# Yaesu_to_CIV.net
KiCad netlist of a schematic drawn in EAGLE
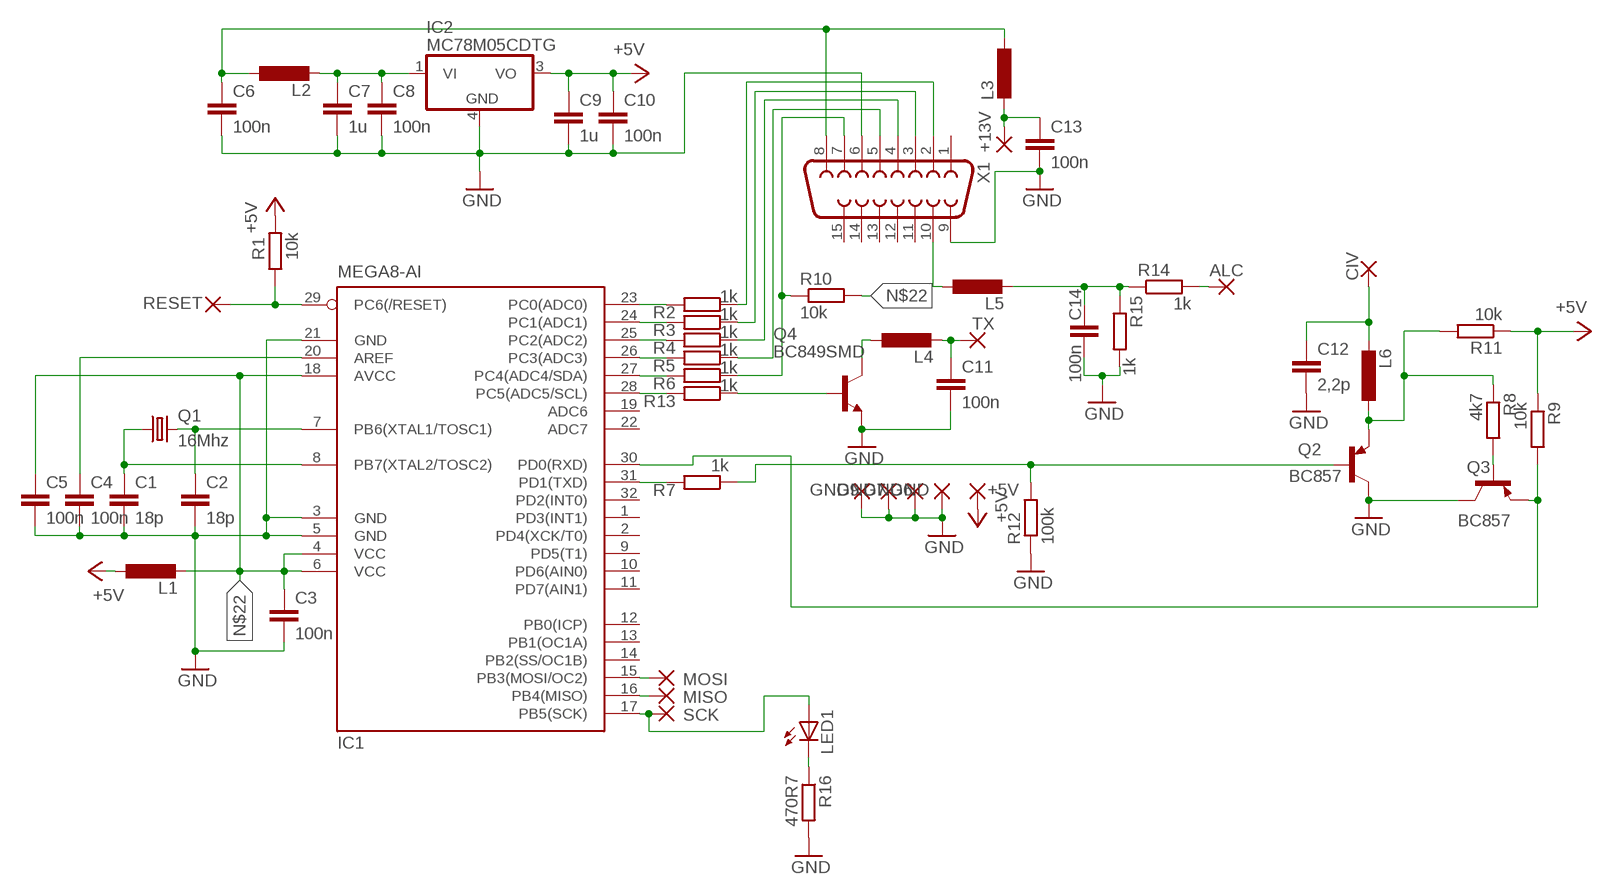
[diagram p0: schematic, sheet 1]

(export (version "E")
  (design (tool "Eeschema 10.0.6"))
  (components
    (comp (ref "+5V")
      (value "SMD2")
      (footprint "eagle-import:SMD1,27-2,54")
      (libsource (lib "eagle-import") (part "SMD2"))
    )
    (comp (ref "+13V")
      (value "SMD2")
      (footprint "eagle-import:SMD1,27-2,54")
      (libsource (lib "eagle-import") (part "SMD2"))
    )
    (comp (ref "ALC")
      (value "SMD2")
      (footprint "eagle-import:SMD1,27-2,54")
      (libsource (lib "eagle-import") (part "SMD2"))
    )
    (comp (ref "C1")
      (value "18p")
      (footprint "eagle-import:C0603K")
      (libsource (lib "eagle-import") (part "C-EUC0603K"))
    )
    (comp (ref "C2")
      (value "18p")
      (footprint "eagle-import:C0603K")
      (libsource (lib "eagle-import") (part "C-EUC0603K"))
    )
    (comp (ref "C3")
      (value "100n")
      (footprint "eagle-import:C0603K")
      (libsource (lib "eagle-import") (part "C-EUC0603K"))
    )
    (comp (ref "C4")
      (value "100n")
      (footprint "eagle-import:C0603K")
      (libsource (lib "eagle-import") (part "C-EUC0603K"))
    )
    (comp (ref "C5")
      (value "100n")
      (footprint "eagle-import:C0603K")
      (libsource (lib "eagle-import") (part "C-EUC0603K"))
    )
    (comp (ref "C6")
      (value "100n")
      (footprint "eagle-import:C0603K")
      (libsource (lib "eagle-import") (part "C-EUC0603K"))
    )
    (comp (ref "C7")
      (value "1u")
      (footprint "eagle-import:C0805K")
      (libsource (lib "eagle-import") (part "C-EUC0805K"))
    )
    (comp (ref "C8")
      (value "100n")
      (footprint "eagle-import:C0603K")
      (libsource (lib "eagle-import") (part "C-EUC0603K"))
    )
    (comp (ref "C9")
      (value "1u")
      (footprint "eagle-import:C0805K")
      (libsource (lib "eagle-import") (part "C-EUC0805K"))
    )
    (comp (ref "C10")
      (value "100n")
      (footprint "eagle-import:C0603K")
      (libsource (lib "eagle-import") (part "C-EUC0603K"))
    )
    (comp (ref "C11")
      (value "100n")
      (footprint "eagle-import:C0603K")
      (libsource (lib "eagle-import") (part "C-EUC0603K"))
    )
    (comp (ref "C12")
      (value "2,2p")
      (footprint "eagle-import:C0603K")
      (libsource (lib "eagle-import") (part "C-EUC0603K"))
    )
    (comp (ref "C13")
      (value "100n")
      (footprint "eagle-import:C0603K")
      (libsource (lib "eagle-import") (part "C-EUC0603K"))
    )
    (comp (ref "C14")
      (value "100n")
      (footprint "eagle-import:C0603K")
      (libsource (lib "eagle-import") (part "C-EUC0603K"))
    )
    (comp (ref "CIV")
      (value "SMD2")
      (footprint "eagle-import:SMD1,27-2,54")
      (libsource (lib "eagle-import") (part "SMD2"))
    )
    (comp (ref "GND")
      (value "SMD2")
      (footprint "eagle-import:SMD1,27-2,54")
      (libsource (lib "eagle-import") (part "SMD2"))
    )
    (comp (ref "GND6")
      (value "SMD2")
      (footprint "eagle-import:SMD1,27-2,54")
      (libsource (lib "eagle-import") (part "SMD2"))
    )
    (comp (ref "GND7")
      (value "SMD2")
      (footprint "eagle-import:SMD1,27-2,54")
      (libsource (lib "eagle-import") (part "SMD2"))
    )
    (comp (ref "GND9")
      (value "SMD2")
      (footprint "eagle-import:SMD1,27-2,54")
      (libsource (lib "eagle-import") (part "SMD2"))
    )
    (comp (ref "IC1")
      (value "MEGA8-AI")
      (footprint "eagle-import:TQFP32-08")
      (fields (field (name "MPN") "ATMEGA8-16AU"))
      (libsource (lib "eagle-import") (part "MEGA8-AI"))
    )
    (comp (ref "IC2")
      (value "MC78M05CDTG")
      (footprint "eagle-import:DPACK_3")
      (libsource (lib "eagle-import") (part "MC78M05CDTG"))
    )
    (comp (ref "L1")
      (value "L-EUL2012C")
      (footprint "eagle-import:L2012C")
      (libsource (lib "eagle-import") (part "L-EUL2012C"))
    )
    (comp (ref "L2")
      (value "L-EUL1812")
      (footprint "eagle-import:L1812")
      (libsource (lib "eagle-import") (part "L-EUL1812"))
    )
    (comp (ref "L3")
      (value "L-EUL1812")
      (footprint "eagle-import:L1812")
      (libsource (lib "eagle-import") (part "L-EUL1812"))
    )
    (comp (ref "L4")
      (value "L-EUL2012C")
      (footprint "eagle-import:L2012C")
      (libsource (lib "eagle-import") (part "L-EUL2012C"))
    )
    (comp (ref "L5")
      (value "L-EUL2012C")
      (footprint "eagle-import:L2012C")
      (libsource (lib "eagle-import") (part "L-EUL2012C"))
    )
    (comp (ref "L6")
      (value "L-EUL2012C")
      (footprint "eagle-import:L2012C")
      (libsource (lib "eagle-import") (part "L-EUL2012C"))
    )
    (comp (ref "LED1")
      (value "LEDCHIP-LED0603")
      (footprint "eagle-import:CHIP-LED0603")
      (libsource (lib "eagle-import") (part "LEDCHIP-LED0603"))
    )
    (comp (ref "MISO")
      (value "SMD2")
      (footprint "eagle-import:SMD1,27-2,54")
      (libsource (lib "eagle-import") (part "SMD2"))
    )
    (comp (ref "MOSI")
      (value "SMD2")
      (footprint "eagle-import:SMD1,27-2,54")
      (libsource (lib "eagle-import") (part "SMD2"))
    )
    (comp (ref "Q1")
      (value "16Mhz")
      (footprint "eagle-import:CTS406")
      (libsource (lib "eagle-import") (part "CRYSTALCTS406"))
    )
    (comp (ref "Q2")
      (value "BC857")
      (footprint "eagle-import:SOT23-BEC")
      (libsource (lib "eagle-import") (part "BC857SMDA"))
    )
    (comp (ref "Q3")
      (value "BC857")
      (footprint "eagle-import:SOT23-BEC")
      (libsource (lib "eagle-import") (part "BC857SMDA"))
    )
    (comp (ref "Q4")
      (value "BC849SMD")
      (footprint "eagle-import:SOT23-BEC")
      (libsource (lib "eagle-import") (part "BC849SMD"))
    )
    (comp (ref "R1")
      (value "10k")
      (footprint "eagle-import:R0603")
      (libsource (lib "eagle-import") (part "R-EU_R0603"))
    )
    (comp (ref "R2")
      (value "1k")
      (footprint "eagle-import:R0603")
      (libsource (lib "eagle-import") (part "R-EU_R0603"))
    )
    (comp (ref "R3")
      (value "1k")
      (footprint "eagle-import:R0603")
      (libsource (lib "eagle-import") (part "R-EU_R0603"))
    )
    (comp (ref "R4")
      (value "1k")
      (footprint "eagle-import:R0603")
      (libsource (lib "eagle-import") (part "R-EU_R0603"))
    )
    (comp (ref "R5")
      (value "1k")
      (footprint "eagle-import:R0603")
      (libsource (lib "eagle-import") (part "R-EU_R0603"))
    )
    (comp (ref "R6")
      (value "1k")
      (footprint "eagle-import:R0603")
      (libsource (lib "eagle-import") (part "R-EU_R0603"))
    )
    (comp (ref "R7")
      (value "1k")
      (footprint "eagle-import:R0603")
      (libsource (lib "eagle-import") (part "R-EU_R0603"))
    )
    (comp (ref "R8")
      (value "4k7")
      (footprint "eagle-import:R0603")
      (libsource (lib "eagle-import") (part "R-EU_R0603"))
    )
    (comp (ref "R9")
      (value "10k")
      (footprint "eagle-import:R0603")
      (libsource (lib "eagle-import") (part "R-EU_R0603"))
    )
    (comp (ref "R10")
      (value "10k")
      (footprint "eagle-import:R0603")
      (libsource (lib "eagle-import") (part "R-EU_R0603"))
    )
    (comp (ref "R11")
      (value "10k")
      (footprint "eagle-import:R0603")
      (libsource (lib "eagle-import") (part "R-EU_R0603"))
    )
    (comp (ref "R12")
      (value "100k")
      (footprint "eagle-import:R0603")
      (libsource (lib "eagle-import") (part "R-EU_R0603"))
    )
    (comp (ref "R13")
      (value "1k")
      (footprint "eagle-import:R0603")
      (libsource (lib "eagle-import") (part "R-EU_R0603"))
    )
    (comp (ref "R14")
      (value "1k")
      (footprint "eagle-import:R0603")
      (libsource (lib "eagle-import") (part "R-EU_R0603"))
    )
    (comp (ref "R15")
      (value "1k")
      (footprint "eagle-import:R0603")
      (libsource (lib "eagle-import") (part "R-EU_R0603"))
    )
    (comp (ref "R16")
      (value "470R7")
      (footprint "eagle-import:R0603")
      (libsource (lib "eagle-import") (part "R-EU_R0603"))
    )
    (comp (ref "RESET")
      (value "SMD2")
      (footprint "eagle-import:SMD1,27-2,54")
      (libsource (lib "eagle-import") (part "SMD2"))
    )
    (comp (ref "SCK")
      (value "SMD2")
      (footprint "eagle-import:SMD1,27-2,54")
      (libsource (lib "eagle-import") (part "SMD2"))
    )
    (comp (ref "TX")
      (value "SMD2")
      (footprint "eagle-import:SMD1,27-2,54")
      (libsource (lib "eagle-import") (part "SMD2"))
    )
    (comp (ref "X1")
      (value "F15D")
      (footprint "eagle-import:F15D")
      (libsource (lib "eagle-import") (part "F15D"))
    )
  )
  (nets
    (net (code "1") (name "+5V") (class "Default")
      (node (ref "+5V") (pin "1") (pinfunction "P_1") (pintype "passive"))
      (node (ref "C10") (pin "1") (pinfunction "1_1") (pintype "passive"))
      (node (ref "C9") (pin "1") (pinfunction "1_1") (pintype "passive"))
      (node (ref "IC2") (pin "3") (pinfunction "VO_3") (pintype "passive"))
      (node (ref "L1") (pin "1") (pinfunction "1_1") (pintype "passive"))
      (node (ref "R1") (pin "2") (pinfunction "2_2") (pintype "passive"))
      (node (ref "R11") (pin "1") (pinfunction "1_1") (pintype "passive"))
      (node (ref "R9") (pin "1") (pinfunction "1_1") (pintype "passive"))
    )
    (net (code "2") (name "GND") (class "Default")
      (node (ref "C1") (pin "2") (pinfunction "2_2") (pintype "passive"))
      (node (ref "C10") (pin "2") (pinfunction "2_2") (pintype "passive"))
      (node (ref "C11") (pin "2") (pinfunction "2_2") (pintype "passive"))
      (node (ref "C12") (pin "2") (pinfunction "2_2") (pintype "passive"))
      (node (ref "C13") (pin "2") (pinfunction "2_2") (pintype "passive"))
      (node (ref "C14") (pin "2") (pinfunction "2_2") (pintype "passive"))
      (node (ref "C2") (pin "2") (pinfunction "2_2") (pintype "passive"))
      (node (ref "C3") (pin "2") (pinfunction "2_2") (pintype "passive"))
      (node (ref "C4") (pin "2") (pinfunction "2_2") (pintype "passive"))
      (node (ref "C5") (pin "2") (pinfunction "2_2") (pintype "passive"))
      (node (ref "C6") (pin "2") (pinfunction "2_2") (pintype "passive"))
      (node (ref "C7") (pin "2") (pinfunction "2_2") (pintype "passive"))
      (node (ref "C8") (pin "2") (pinfunction "2_2") (pintype "passive"))
      (node (ref "C9") (pin "2") (pinfunction "2_2") (pintype "passive"))
      (node (ref "GND") (pin "1") (pinfunction "P_1") (pintype "passive"))
      (node (ref "GND6") (pin "1") (pinfunction "P_1") (pintype "passive"))
      (node (ref "GND7") (pin "1") (pinfunction "P_1") (pintype "passive"))
      (node (ref "GND9") (pin "1") (pinfunction "P_1") (pintype "passive"))
      (node (ref "IC1") (pin "21") (pinfunction "GND_21") (pintype "power_in"))
      (node (ref "IC1") (pin "3") (pinfunction "GND_3") (pintype "power_in"))
      (node (ref "IC1") (pin "5") (pinfunction "GND_5") (pintype "power_in"))
      (node (ref "IC2") (pin "4") (pinfunction "GND_4") (pintype "passive"))
      (node (ref "Q2") (pin "C") (pinfunction "C_C") (pintype "passive"))
      (node (ref "Q3") (pin "C") (pinfunction "C_C") (pintype "passive"))
      (node (ref "Q4") (pin "E") (pinfunction "E_E") (pintype "passive"))
      (node (ref "R12") (pin "1") (pinfunction "1_1") (pintype "passive"))
      (node (ref "R15") (pin "2") (pinfunction "2_2") (pintype "passive"))
      (node (ref "R16") (pin "2") (pinfunction "2_2") (pintype "passive"))
      (node (ref "X1") (pin "6") (pinfunction "6_6") (pintype "passive"))
      (node (ref "X1") (pin "9") (pinfunction "9_9") (pintype "passive"))
    )
    (net (code "3") (name "N$22") (class "Default")
      (node (ref "C3") (pin "1") (pinfunction "1_1") (pintype "passive"))
      (node (ref "C5") (pin "1") (pinfunction "1_1") (pintype "passive"))
      (node (ref "IC1") (pin "18") (pinfunction "AVCC_18") (pintype "power_in"))
      (node (ref "IC1") (pin "4") (pinfunction "VCC_4") (pintype "power_in"))
      (node (ref "IC1") (pin "6") (pinfunction "VCC_6") (pintype "power_in"))
      (node (ref "L1") (pin "2") (pinfunction "2_2") (pintype "passive"))
      (node (ref "R10") (pin "2") (pinfunction "2_2") (pintype "passive"))
    )
    (net (code "4") (name "Net-(+13V-P)") (class "Default")
      (node (ref "+13V") (pin "1") (pinfunction "P_1") (pintype "passive"))
      (node (ref "C13") (pin "1") (pinfunction "1_1") (pintype "passive"))
      (node (ref "L3") (pin "2") (pinfunction "2_2") (pintype "passive"))
    )
    (net (code "5") (name "Net-(ALC-P)") (class "Default")
      (node (ref "ALC") (pin "1") (pinfunction "P_1") (pintype "passive"))
      (node (ref "R14") (pin "2") (pinfunction "2_2") (pintype "passive"))
    )
    (net (code "6") (name "Net-(C6-Pad1)") (class "Default")
      (node (ref "C6") (pin "1") (pinfunction "1_1") (pintype "passive"))
      (node (ref "L2") (pin "1") (pinfunction "1_1") (pintype "passive"))
      (node (ref "L3") (pin "1") (pinfunction "1_1") (pintype "passive"))
      (node (ref "X1") (pin "8") (pinfunction "8_8") (pintype "passive"))
    )
    (net (code "7") (name "Net-(C14-Pad1)") (class "Default")
      (node (ref "C14") (pin "1") (pinfunction "1_1") (pintype "passive"))
      (node (ref "L5") (pin "2") (pinfunction "2_2") (pintype "passive"))
      (node (ref "R14") (pin "1") (pinfunction "1_1") (pintype "passive"))
      (node (ref "R15") (pin "1") (pinfunction "1_1") (pintype "passive"))
    )
    (net (code "8") (name "Net-(CIV-P)") (class "Default")
      (node (ref "C12") (pin "1") (pinfunction "1_1") (pintype "passive"))
      (node (ref "CIV") (pin "1") (pinfunction "P_1") (pintype "passive"))
      (node (ref "L6") (pin "2") (pinfunction "2_2") (pintype "passive"))
    )
    (net (code "9") (name "Net-(IC1-AREF)") (class "Default")
      (node (ref "C4") (pin "1") (pinfunction "1_1") (pintype "passive"))
      (node (ref "IC1") (pin "20") (pinfunction "AREF_20") (pintype "passive"))
    )
    (net (code "10") (name "Net-(IC1-PB3(MOSI{slash}OC2))") (class "Default")
      (node (ref "IC1") (pin "15") (pinfunction "PB3(MOSI/OC2)_15") (pintype "bidirectional"))
      (node (ref "MOSI") (pin "1") (pinfunction "P_1") (pintype "passive"))
    )
    (net (code "11") (name "Net-(IC1-PB4(MISO))") (class "Default")
      (node (ref "IC1") (pin "16") (pinfunction "PB4(MISO)_16") (pintype "bidirectional"))
      (node (ref "MISO") (pin "1") (pinfunction "P_1") (pintype "passive"))
    )
    (net (code "12") (name "Net-(IC1-PB5(SCK))") (class "Default")
      (node (ref "IC1") (pin "17") (pinfunction "PB5(SCK)_17") (pintype "bidirectional"))
      (node (ref "LED1") (pin "A") (pinfunction "A_A") (pintype "passive"))
      (node (ref "SCK") (pin "1") (pinfunction "P_1") (pintype "passive"))
    )
    (net (code "13") (name "Net-(IC1-PB6(XTAL1{slash}TOSC1))") (class "Default")
      (node (ref "C2") (pin "1") (pinfunction "1_1") (pintype "passive"))
      (node (ref "IC1") (pin "7") (pinfunction "PB6(XTAL1/TOSC1)_7") (pintype "bidirectional"))
      (node (ref "Q1") (pin "3") (pinfunction "2_3") (pintype "passive"))
    )
    (net (code "14") (name "Net-(IC1-PB7(XTAL2{slash}TOSC2))") (class "Default")
      (node (ref "C1") (pin "1") (pinfunction "1_1") (pintype "passive"))
      (node (ref "IC1") (pin "8") (pinfunction "PB7(XTAL2/TOSC2)_8") (pintype "bidirectional"))
      (node (ref "Q1") (pin "1") (pinfunction "1_1") (pintype "passive"))
    )
    (net (code "15") (name "Net-(IC1-PC0(ADC0))") (class "Default")
      (node (ref "IC1") (pin "23") (pinfunction "PC0(ADC0)_23") (pintype "bidirectional"))
      (node (ref "R2") (pin "2") (pinfunction "2_2") (pintype "passive"))
    )
    (net (code "16") (name "Net-(IC1-PC1(ADC1))") (class "Default")
      (node (ref "IC1") (pin "24") (pinfunction "PC1(ADC1)_24") (pintype "bidirectional"))
      (node (ref "R3") (pin "2") (pinfunction "2_2") (pintype "passive"))
    )
    (net (code "17") (name "Net-(IC1-PC2(ADC2))") (class "Default")
      (node (ref "IC1") (pin "25") (pinfunction "PC2(ADC2)_25") (pintype "bidirectional"))
      (node (ref "R4") (pin "2") (pinfunction "2_2") (pintype "passive"))
    )
    (net (code "18") (name "Net-(IC1-PC3(ADC3))") (class "Default")
      (node (ref "IC1") (pin "26") (pinfunction "PC3(ADC3)_26") (pintype "bidirectional"))
      (node (ref "R5") (pin "2") (pinfunction "2_2") (pintype "passive"))
    )
    (net (code "19") (name "Net-(IC1-PC4(ADC4{slash}SDA))") (class "Default")
      (node (ref "IC1") (pin "27") (pinfunction "PC4(ADC4/SDA)_27") (pintype "bidirectional"))
      (node (ref "R6") (pin "2") (pinfunction "2_2") (pintype "passive"))
    )
    (net (code "20") (name "Net-(IC1-PC5(ADC5{slash}SCL))") (class "Default")
      (node (ref "IC1") (pin "28") (pinfunction "PC5(ADC5/SCL)_28") (pintype "bidirectional"))
      (node (ref "R13") (pin "2") (pinfunction "2_2") (pintype "passive"))
    )
    (net (code "21") (name "Net-(IC1-PC6({slash}RESET))") (class "Default")
      (node (ref "IC1") (pin "29") (pinfunction "PC6(/RESET)_29") (pintype "bidirectional"))
      (node (ref "R1") (pin "1") (pinfunction "1_1") (pintype "passive"))
      (node (ref "RESET") (pin "1") (pinfunction "P_1") (pintype "passive"))
    )
    (net (code "22") (name "Net-(IC1-PD0(RXD))") (class "Default")
      (node (ref "IC1") (pin "30") (pinfunction "PD0(RXD)_30") (pintype "bidirectional"))
      (node (ref "Q3") (pin "E") (pinfunction "E_E") (pintype "passive"))
      (node (ref "R9") (pin "2") (pinfunction "2_2") (pintype "passive"))
    )
    (net (code "23") (name "Net-(IC1-PD1(TXD))") (class "Default")
      (node (ref "IC1") (pin "31") (pinfunction "PD1(TXD)_31") (pintype "bidirectional"))
      (node (ref "R7") (pin "2") (pinfunction "2_2") (pintype "passive"))
    )
    (net (code "24") (name "Net-(IC2-VI)") (class "Default")
      (node (ref "C7") (pin "1") (pinfunction "1_1") (pintype "passive"))
      (node (ref "C8") (pin "1") (pinfunction "1_1") (pintype "passive"))
      (node (ref "IC2") (pin "1") (pinfunction "VI_1") (pintype "input"))
      (node (ref "L2") (pin "2") (pinfunction "2_2") (pintype "passive"))
    )
    (net (code "25") (name "Net-(L4-Pad1)") (class "Default")
      (node (ref "L4") (pin "1") (pinfunction "1_1") (pintype "passive"))
      (node (ref "Q4") (pin "C") (pinfunction "C_C") (pintype "passive"))
    )
    (net (code "26") (name "Net-(L5-Pad1)") (class "Default")
      (node (ref "L5") (pin "1") (pinfunction "1_1") (pintype "passive"))
      (node (ref "X1") (pin "10") (pinfunction "10_10") (pintype "passive"))
    )
    (net (code "27") (name "Net-(L6-Pad1)") (class "Default")
      (node (ref "L6") (pin "1") (pinfunction "1_1") (pintype "passive"))
      (node (ref "Q2") (pin "E") (pinfunction "E_E") (pintype "passive"))
      (node (ref "R11") (pin "2") (pinfunction "2_2") (pintype "passive"))
      (node (ref "R8") (pin "1") (pinfunction "1_1") (pintype "passive"))
    )
    (net (code "28") (name "Net-(LED1-PadC)") (class "Default")
      (node (ref "LED1") (pin "C") (pinfunction "C_C") (pintype "passive"))
      (node (ref "R16") (pin "1") (pinfunction "1_1") (pintype "passive"))
    )
    (net (code "29") (name "Net-(Q2-PadB)") (class "Default")
      (node (ref "Q2") (pin "B") (pinfunction "B_B") (pintype "passive"))
      (node (ref "R12") (pin "2") (pinfunction "2_2") (pintype "passive"))
      (node (ref "R7") (pin "1") (pinfunction "1_1") (pintype "passive"))
    )
    (net (code "30") (name "Net-(Q3-PadB)") (class "Default")
      (node (ref "Q3") (pin "B") (pinfunction "B_B") (pintype "passive"))
      (node (ref "R8") (pin "2") (pinfunction "2_2") (pintype "passive"))
    )
    (net (code "31") (name "Net-(Q4-PadB)") (class "Default")
      (node (ref "Q4") (pin "B") (pinfunction "B_B") (pintype "passive"))
      (node (ref "R13") (pin "1") (pinfunction "1_1") (pintype "passive"))
    )
    (net (code "32") (name "Net-(R2-Pad1)") (class "Default")
      (node (ref "R2") (pin "1") (pinfunction "1_1") (pintype "passive"))
      (node (ref "X1") (pin "2") (pinfunction "2_2") (pintype "passive"))
    )
    (net (code "33") (name "Net-(R3-Pad1)") (class "Default")
      (node (ref "R3") (pin "1") (pinfunction "1_1") (pintype "passive"))
      (node (ref "X1") (pin "3") (pinfunction "3_3") (pintype "passive"))
    )
    (net (code "34") (name "Net-(R4-Pad1)") (class "Default")
      (node (ref "R4") (pin "1") (pinfunction "1_1") (pintype "passive"))
      (node (ref "X1") (pin "4") (pinfunction "4_4") (pintype "passive"))
    )
    (net (code "35") (name "Net-(R5-Pad1)") (class "Default")
      (node (ref "R5") (pin "1") (pinfunction "1_1") (pintype "passive"))
      (node (ref "X1") (pin "5") (pinfunction "5_5") (pintype "passive"))
    )
    (net (code "36") (name "Net-(R10-Pad1)") (class "Default")
      (node (ref "R10") (pin "1") (pinfunction "1_1") (pintype "passive"))
      (node (ref "R6") (pin "1") (pinfunction "1_1") (pintype "passive"))
      (node (ref "X1") (pin "7") (pinfunction "7_7") (pintype "passive"))
    )
    (net (code "37") (name "Net-(TX-P)") (class "Default")
      (node (ref "C11") (pin "1") (pinfunction "1_1") (pintype "passive"))
      (node (ref "L4") (pin "2") (pinfunction "2_2") (pintype "passive"))
      (node (ref "TX") (pin "1") (pinfunction "P_1") (pintype "passive"))
    )
    (net (code "38") (name "unconnected-(IC1-ADC6-Pad19)") (class "Default")
      (node (ref "IC1") (pin "19") (pinfunction "ADC6_19") (pintype "bidirectional"))
    )
    (net (code "39") (name "unconnected-(IC1-ADC7-Pad22)") (class "Default")
      (node (ref "IC1") (pin "22") (pinfunction "ADC7_22") (pintype "bidirectional"))
    )
    (net (code "40") (name "unconnected-(IC1-PB0(ICP)-Pad12)") (class "Default")
      (node (ref "IC1") (pin "12") (pinfunction "PB0(ICP)_12") (pintype "bidirectional"))
    )
    (net (code "41") (name "unconnected-(IC1-PB1(OC1A)-Pad13)") (class "Default")
      (node (ref "IC1") (pin "13") (pinfunction "PB1(OC1A)_13") (pintype "bidirectional"))
    )
    (net (code "42") (name "unconnected-(IC1-PB2(SS{slash}OC1B)-Pad14)") (class "Default")
      (node (ref "IC1") (pin "14") (pinfunction "PB2(SS/OC1B)_14") (pintype "bidirectional"))
    )
    (net (code "43") (name "unconnected-(IC1-PD2(INT0)-Pad32)") (class "Default")
      (node (ref "IC1") (pin "32") (pinfunction "PD2(INT0)_32") (pintype "bidirectional"))
    )
    (net (code "44") (name "unconnected-(IC1-PD3(INT1)-Pad1)") (class "Default")
      (node (ref "IC1") (pin "1") (pinfunction "PD3(INT1)_1") (pintype "bidirectional"))
    )
    (net (code "45") (name "unconnected-(IC1-PD4(XCK{slash}T0)-Pad2)") (class "Default")
      (node (ref "IC1") (pin "2") (pinfunction "PD4(XCK/T0)_2") (pintype "bidirectional"))
    )
    (net (code "46") (name "unconnected-(IC1-PD5(T1)-Pad9)") (class "Default")
      (node (ref "IC1") (pin "9") (pinfunction "PD5(T1)_9") (pintype "bidirectional"))
    )
    (net (code "47") (name "unconnected-(IC1-PD6(AIN0)-Pad10)") (class "Default")
      (node (ref "IC1") (pin "10") (pinfunction "PD6(AIN0)_10") (pintype "bidirectional"))
    )
    (net (code "48") (name "unconnected-(IC1-PD7(AIN1)-Pad11)") (class "Default")
      (node (ref "IC1") (pin "11") (pinfunction "PD7(AIN1)_11") (pintype "bidirectional"))
    )
    (net (code "49") (name "unconnected-(X1-Pad1)") (class "Default")
      (node (ref "X1") (pin "1") (pinfunction "1_1") (pintype "passive"))
    )
    (net (code "50") (name "unconnected-(X1-Pad11)") (class "Default")
      (node (ref "X1") (pin "11") (pinfunction "11_11") (pintype "passive"))
    )
    (net (code "51") (name "unconnected-(X1-Pad12)") (class "Default")
      (node (ref "X1") (pin "12") (pinfunction "12_12") (pintype "passive"))
    )
    (net (code "52") (name "unconnected-(X1-Pad13)") (class "Default")
      (node (ref "X1") (pin "13") (pinfunction "13_13") (pintype "passive"))
    )
    (net (code "53") (name "unconnected-(X1-Pad14)") (class "Default")
      (node (ref "X1") (pin "14") (pinfunction "14_14") (pintype "passive"))
    )
    (net (code "54") (name "unconnected-(X1-Pad15)") (class "Default")
      (node (ref "X1") (pin "15") (pinfunction "15_15") (pintype "passive"))
    )
  )
)
